# Main.net
KiCad netlist of a schematic drawn in Altium Designer
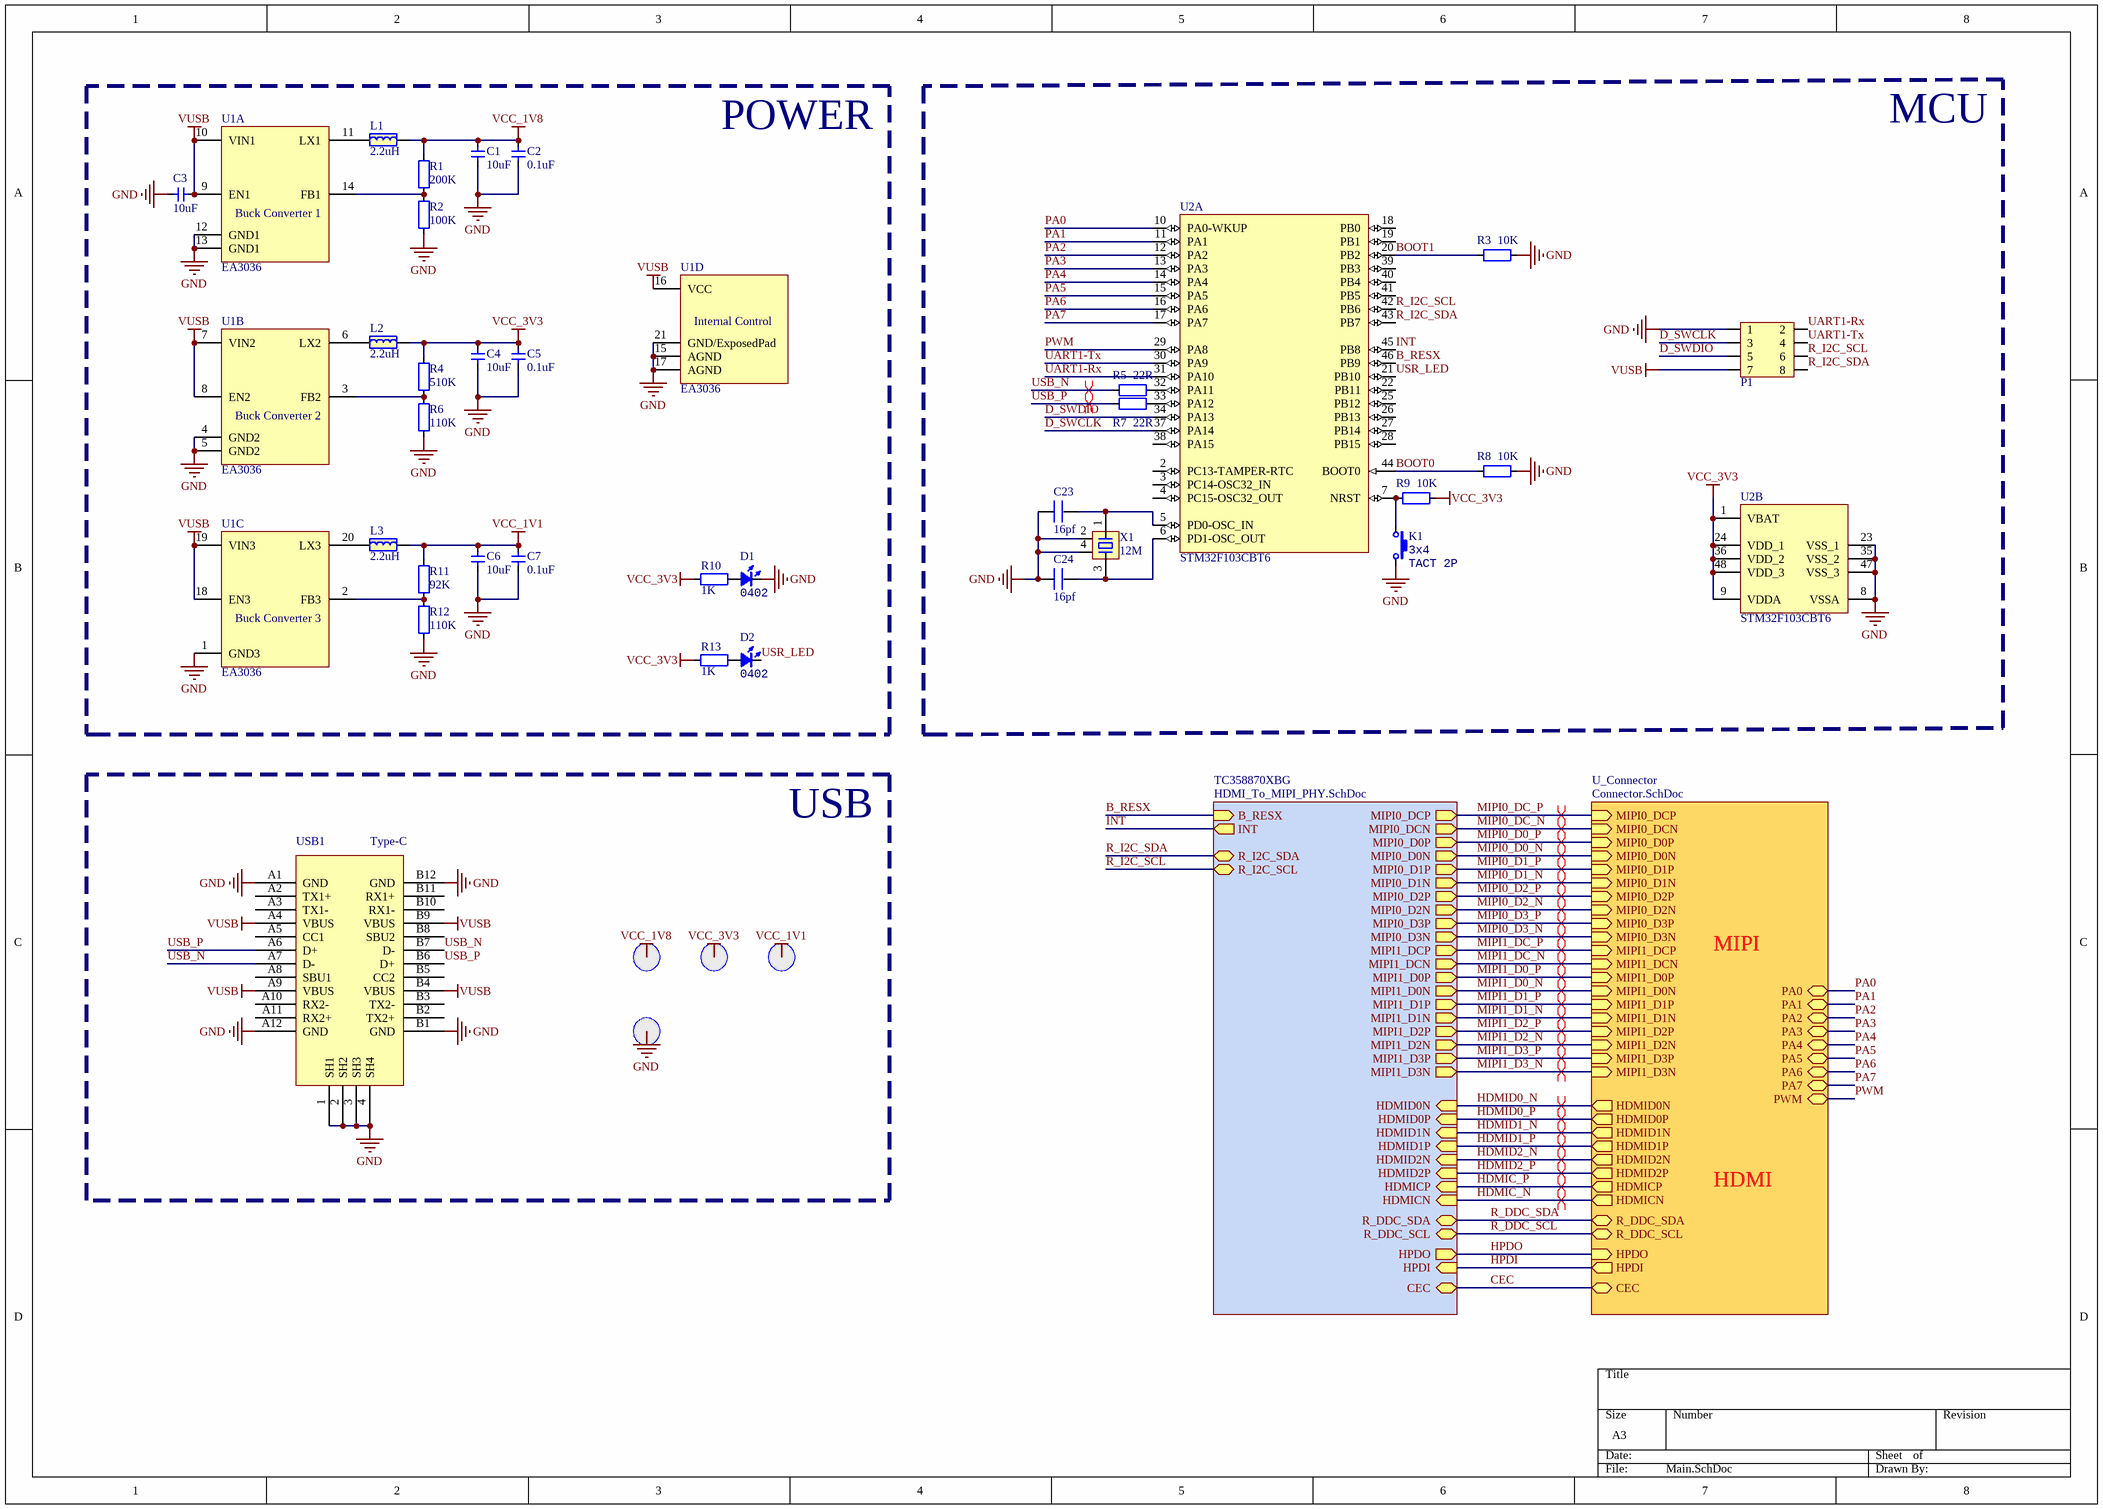
[diagram p0: Main.SchDoc]

(export (version "E")
  (design (tool "Eeschema 10.0.6"))
  (components
    (comp (ref "C1")
      (value "10uF")
      (footprint "CAP_0402")
      (description "Capacitor")
      (libsource (lib "MyPcbLib") (part "电容-0402"))
    )
    (comp (ref "C2")
      (value "0.1uF")
      (footprint "CAP_0402")
      (description "Capacitor")
      (libsource (lib "MyPcbLib") (part "电容-0402"))
    )
    (comp (ref "C3")
      (value "10uF")
      (footprint "CAP_0402")
      (description "Capacitor")
      (libsource (lib "MyPcbLib") (part "电容-0402"))
    )
    (comp (ref "C4")
      (value "10uF")
      (footprint "CAP_0402")
      (description "Capacitor")
      (libsource (lib "MyPcbLib") (part "电容-0402"))
    )
    (comp (ref "C5")
      (value "0.1uF")
      (footprint "CAP_0402")
      (description "Capacitor")
      (libsource (lib "MyPcbLib") (part "电容-0402"))
    )
    (comp (ref "C6")
      (value "10uF")
      (footprint "CAP_0402")
      (description "Capacitor")
      (libsource (lib "MyPcbLib") (part "电容-0402"))
    )
    (comp (ref "C7")
      (value "0.1uF")
      (footprint "CAP_0402")
      (description "Capacitor")
      (libsource (lib "MyPcbLib") (part "电容-0402"))
    )
    (comp (ref "C23") (value "16pf") (footprint "0603_CAP") (libsource (lib "STM32F429核心板封装库") (part "C")))
    (comp (ref "C24") (value "16pf") (footprint "0603_CAP") (libsource (lib "STM32F429核心板封装库") (part "C")))
    (comp (ref "D1")
      (value "color?")
      (footprint "SMDLED-0603")
      (description "LED")
      (fields (field (name "TYPE") "0402"))
      (libsource (lib "KitSprout") (part "LED_0402"))
    )
    (comp (ref "D2")
      (value "color?")
      (footprint "SMDLED-0603")
      (description "LED")
      (fields (field (name "TYPE") "0402"))
      (libsource (lib "KitSprout") (part "LED_0402"))
    )
    (comp (ref "K1")
      (value "3x4")
      (footprint "ButtonTACT_3x4x2_180H")
      (description "Button")
      (fields (field (name "TYPE") "TACT 2P") (field (name "Comment") "TACT 2P"))
      (libsource (lib "KitSprout") (part "ButtonTACT_3x4x2_180"))
    )
    (comp (ref "L1")
      (value "2.2uH")
      (footprint "2520-L")
      (description "磁珠")
      (libsource (lib "MyPcbLib") (part "电感-2520"))
    )
    (comp (ref "L2")
      (value "2.2uH")
      (footprint "2520-L")
      (description "磁珠")
      (libsource (lib "MyPcbLib") (part "电感-2520"))
    )
    (comp (ref "L3")
      (value "2.2uH")
      (footprint "2520-L")
      (description "磁珠")
      (libsource (lib "MyPcbLib") (part "电感-2520"))
    )
    (comp (ref "P1")
      (value "HDR2x4_2.54")
      (footprint "HDR2X4_2.54_180H")
      (description "Header")
      (libsource (lib "MyPcbLib") (part "HDR2x4_2.54"))
    )
    (comp (ref "R1")
      (value "200K")
      (footprint "RES_0402")
      (description "Resistor")
      (libsource (lib "MyPcbLib") (part "电阻-0402"))
    )
    (comp (ref "R2")
      (value "100K")
      (footprint "RES_0402")
      (description "Resistor")
      (libsource (lib "MyPcbLib") (part "电阻-0402"))
    )
    (comp (ref "R3")
      (value "10K")
      (footprint "RES_0402")
      (description "Resistor")
      (libsource (lib "") (part "电阻-0402_1"))
    )
    (comp (ref "R4")
      (value "510K")
      (footprint "RES_0402")
      (description "Resistor")
      (libsource (lib "MyPcbLib") (part "电阻-0402"))
    )
    (comp (ref "R5")
      (value "22R")
      (footprint "RES_0402")
      (description "Resistor")
      (libsource (lib "") (part "电阻-0402_1"))
    )
    (comp (ref "R6")
      (value "110K")
      (footprint "RES_0402")
      (description "Resistor")
      (libsource (lib "MyPcbLib") (part "电阻-0402"))
    )
    (comp (ref "R7")
      (value "22R")
      (footprint "RES_0402")
      (description "Resistor")
      (libsource (lib "") (part "电阻-0402_1"))
    )
    (comp (ref "R8")
      (value "10K")
      (footprint "RES_0402")
      (description "Resistor")
      (libsource (lib "") (part "电阻-0402_1"))
    )
    (comp (ref "R9")
      (value "10K")
      (footprint "RES_0402")
      (description "Resistor")
      (libsource (lib "") (part "电阻-0402_1"))
    )
    (comp (ref "R10")
      (value "1K")
      (footprint "RES_0402")
      (description "Resistor")
      (libsource (lib "") (part "电阻-0402_1"))
    )
    (comp (ref "R11")
      (value "92K")
      (footprint "RES_0402")
      (description "Resistor")
      (libsource (lib "MyPcbLib") (part "电阻-0402"))
    )
    (comp (ref "R12")
      (value "110K")
      (footprint "RES_0402")
      (description "Resistor")
      (libsource (lib "MyPcbLib") (part "电阻-0402"))
    )
    (comp (ref "R13")
      (value "1K")
      (footprint "RES_0402")
      (description "Resistor")
      (libsource (lib "") (part "电阻-0402_1"))
    )
    (comp (ref "T1") (value "测试点") (footprint "TEST_PT") (libsource (lib "MyPcbLib") (part "测试点")))
    (comp (ref "T2") (value "测试点") (footprint "TEST_PT") (libsource (lib "MyPcbLib") (part "测试点")))
    (comp (ref "T3") (value "测试点") (footprint "TEST_PT") (libsource (lib "MyPcbLib") (part "测试点")))
    (comp (ref "T4") (value "测试点") (footprint "TEST_PT") (libsource (lib "MyPcbLib") (part "测试点")))
    (comp (ref "U1") (value "EA3036") (footprint "QFN-20") (libsource (lib "mLib") (part "EA3036")))
    (comp (ref "U2")
      (value "STM32F103CBT6")
      (footprint "LQFP-48")
      (libsource (lib "STMicroelectronics STM32 F1") (part "STM32F103CBT6"))
    )
    (comp (ref "USB1")
      (value "Type-C")
      (footprint "Type-C-TOP")
      (libsource (lib "MyPcbLib") (part "USB-Type-C-TOP"))
    )
    (comp (ref "X1")
      (value "12M")
      (footprint "XTAL3225")
      (description "4脚无源晶振")
      (fields (field (name "版权归属") "源创客"))
      (libsource (lib "10.1 - 保险丝-晶振") (part "XTAL-4P"))
    )
  )
  (nets
    (net (code "1") (name "/BOOT0") (class "Default")
      (node (ref "R8") (pin "1") (pinfunction "1_1") (pintype "passive"))
      (node (ref "U2") (pin "44") (pinfunction "BOOT0_44") (pintype "input"))
    )
    (net (code "2") (name "/BOOT1") (class "Default")
      (node (ref "R3") (pin "1") (pinfunction "1_1") (pintype "passive"))
      (node (ref "U2") (pin "20") (pinfunction "PB2_20") (pintype "bidirectional"))
    )
    (net (code "3") (name "/B_RESX") (class "Default")
      (node (ref "U2") (pin "46") (pinfunction "PB9_46") (pintype "bidirectional"))
    )
    (net (code "5") (name "/D_SWCLK") (class "Default")
      (node (ref "P1") (pin "3") (pinfunction "3_3") (pintype "passive"))
      (node (ref "U2") (pin "37") (pinfunction "PA14_37") (pintype "bidirectional"))
    )
    (net (code "6") (name "/D_SWDIO") (class "Default")
      (node (ref "P1") (pin "5") (pinfunction "5_5") (pintype "passive"))
      (node (ref "U2") (pin "34") (pinfunction "PA13_34") (pintype "bidirectional"))
    )
    (net (code "17") (name "/INT") (class "Default")
      (node (ref "U2") (pin "45") (pinfunction "PB8_45") (pintype "bidirectional"))
    )
    (net (code "38") (name "/PA0") (class "Default")
      (node (ref "U2") (pin "10") (pinfunction "PA0-WKUP_10") (pintype "bidirectional"))
    )
    (net (code "39") (name "/PA1") (class "Default")
      (node (ref "U2") (pin "11") (pinfunction "PA1_11") (pintype "bidirectional"))
    )
    (net (code "40") (name "/PA2") (class "Default")
      (node (ref "U2") (pin "12") (pinfunction "PA2_12") (pintype "bidirectional"))
    )
    (net (code "41") (name "/PA3") (class "Default")
      (node (ref "U2") (pin "13") (pinfunction "PA3_13") (pintype "bidirectional"))
    )
    (net (code "42") (name "/PA4") (class "Default")
      (node (ref "U2") (pin "14") (pinfunction "PA4_14") (pintype "bidirectional"))
    )
    (net (code "43") (name "/PA5") (class "Default")
      (node (ref "U2") (pin "15") (pinfunction "PA5_15") (pintype "bidirectional"))
    )
    (net (code "44") (name "/PA6") (class "Default")
      (node (ref "U2") (pin "16") (pinfunction "PA6_16") (pintype "bidirectional"))
    )
    (net (code "45") (name "/PA7") (class "Default")
      (node (ref "U2") (pin "17") (pinfunction "PA7_17") (pintype "bidirectional"))
    )
    (net (code "46") (name "/PWM") (class "Default")
      (node (ref "U2") (pin "29") (pinfunction "PA8_29") (pintype "bidirectional"))
    )
    (net (code "49") (name "/R_I2C_SCL") (class "Default")
      (node (ref "P1") (pin "6") (pinfunction "6_6") (pintype "passive"))
      (node (ref "U2") (pin "42") (pinfunction "PB6_42") (pintype "bidirectional"))
    )
    (net (code "50") (name "/R_I2C_SDA") (class "Default")
      (node (ref "P1") (pin "8") (pinfunction "8_8") (pintype "passive"))
      (node (ref "U2") (pin "43") (pinfunction "PB7_43") (pintype "bidirectional"))
    )
    (net (code "51") (name "/UART1-Rx") (class "Default")
      (node (ref "P1") (pin "2") (pinfunction "2_2") (pintype "passive"))
      (node (ref "U2") (pin "31") (pinfunction "PA10_31") (pintype "bidirectional"))
    )
    (net (code "52") (name "/UART1-Tx") (class "Default")
      (node (ref "P1") (pin "4") (pinfunction "4_4") (pintype "passive"))
      (node (ref "U2") (pin "30") (pinfunction "PA9_30") (pintype "bidirectional"))
    )
    (net (code "53") (name "/USB_N") (class "Default")
      (node (ref "R5") (pin "1") (pinfunction "1_1") (pintype "passive"))
      (node (ref "USB1") (pin "A7") (pinfunction "D-_A7") (pintype "passive"))
      (node (ref "USB1") (pin "B7") (pinfunction "D-_B7") (pintype "passive"))
    )
    (net (code "54") (name "/USB_P") (class "Default")
      (node (ref "R7") (pin "1") (pinfunction "1_1") (pintype "passive"))
      (node (ref "USB1") (pin "A6") (pinfunction "D+_A6") (pintype "passive"))
      (node (ref "USB1") (pin "B6") (pinfunction "D+_B6") (pintype "passive"))
    )
    (net (code "55") (name "/USR_LED") (class "Default")
      (node (ref "D2") (pin "2") (pinfunction "K_2") (pintype "passive"))
      (node (ref "U2") (pin "21") (pinfunction "PB10_21") (pintype "bidirectional"))
    )
    (net (code "56") (name "GND") (class "Default")
      (node (ref "C1") (pin "1") (pinfunction "1_1") (pintype "passive"))
      (node (ref "C2") (pin "2") (pinfunction "2_2") (pintype "passive"))
      (node (ref "C23") (pin "2") (pintype "passive"))
      (node (ref "C24") (pin "2") (pintype "passive"))
      (node (ref "C3") (pin "1") (pinfunction "1_1") (pintype "passive"))
      (node (ref "C4") (pin "1") (pinfunction "1_1") (pintype "passive"))
      (node (ref "C5") (pin "2") (pinfunction "2_2") (pintype "passive"))
      (node (ref "C6") (pin "1") (pinfunction "1_1") (pintype "passive"))
      (node (ref "C7") (pin "2") (pinfunction "2_2") (pintype "passive"))
      (node (ref "D1") (pin "2") (pinfunction "K_2") (pintype "passive"))
      (node (ref "K1") (pin "2") (pinfunction "2_2") (pintype "passive"))
      (node (ref "P1") (pin "1") (pinfunction "1_1") (pintype "passive"))
      (node (ref "R12") (pin "1") (pinfunction "1_1") (pintype "passive"))
      (node (ref "R2") (pin "1") (pinfunction "1_1") (pintype "passive"))
      (node (ref "R3") (pin "2") (pinfunction "2_2") (pintype "passive"))
      (node (ref "R6") (pin "1") (pinfunction "1_1") (pintype "passive"))
      (node (ref "R8") (pin "2") (pinfunction "2_2") (pintype "passive"))
      (node (ref "T4") (pin "0") (pinfunction "0_0") (pintype "passive"))
      (node (ref "U1") (pin "1") (pinfunction "GND3_1") (pintype "power_in"))
      (node (ref "U1") (pin "12") (pinfunction "GND1_12") (pintype "power_in"))
      (node (ref "U1") (pin "13") (pinfunction "GND1_13") (pintype "power_in"))
      (node (ref "U1") (pin "15") (pinfunction "AGND_15") (pintype "power_in"))
      (node (ref "U1") (pin "17") (pinfunction "AGND_17") (pintype "power_in"))
      (node (ref "U1") (pin "21") (pinfunction "GND/ExposedPad_21") (pintype "power_in"))
      (node (ref "U1") (pin "4") (pinfunction "GND2_4") (pintype "power_in"))
      (node (ref "U1") (pin "5") (pinfunction "GND2_5") (pintype "power_in"))
      (node (ref "U2") (pin "23") (pinfunction "VSS_1_23") (pintype "power_in"))
      (node (ref "U2") (pin "35") (pinfunction "VSS_2_35") (pintype "power_in"))
      (node (ref "U2") (pin "47") (pinfunction "VSS_3_47") (pintype "power_in"))
      (node (ref "U2") (pin "8") (pinfunction "VSSA_8") (pintype "power_in"))
      (node (ref "USB1") (pin "1") (pinfunction "SH1_1") (pintype "passive"))
      (node (ref "USB1") (pin "2") (pinfunction "SH2_2") (pintype "passive"))
      (node (ref "USB1") (pin "3") (pinfunction "SH3_3") (pintype "passive"))
      (node (ref "USB1") (pin "4") (pinfunction "SH4_4") (pintype "passive"))
      (node (ref "USB1") (pin "A1") (pinfunction "GND_A1") (pintype "passive"))
      (node (ref "USB1") (pin "A12") (pinfunction "GND_A12") (pintype "passive"))
      (node (ref "USB1") (pin "B1") (pinfunction "GND_B1") (pintype "passive"))
      (node (ref "USB1") (pin "B12") (pinfunction "GND_B12") (pintype "passive"))
      (node (ref "X1") (pin "2") (pinfunction "2_2") (pintype "passive"))
      (node (ref "X1") (pin "4") (pinfunction "4_4") (pintype "passive"))
    )
    (net (code "57") (name "Net-(D1-A)") (class "Default")
      (node (ref "D1") (pin "1") (pinfunction "A_1") (pintype "passive"))
      (node (ref "R10") (pin "2") (pinfunction "2_2") (pintype "passive"))
    )
    (net (code "58") (name "Net-(D2-A)") (class "Default")
      (node (ref "D2") (pin "1") (pinfunction "A_1") (pintype "passive"))
      (node (ref "R13") (pin "2") (pinfunction "2_2") (pintype "passive"))
    )
    (net (code "59") (name "Net-(U1A-FB1)") (class "Default")
      (node (ref "R1") (pin "1") (pinfunction "1_1") (pintype "passive"))
      (node (ref "R2") (pin "2") (pinfunction "2_2") (pintype "passive"))
      (node (ref "U1") (pin "14") (pinfunction "FB1_14") (pintype "passive"))
    )
    (net (code "60") (name "Net-(U1A-LX1)") (class "Default")
      (node (ref "L1") (pin "1") (pintype "passive"))
      (node (ref "U1") (pin "11") (pinfunction "LX1_11") (pintype "passive"))
    )
    (net (code "61") (name "Net-(U1B-FB2)") (class "Default")
      (node (ref "R4") (pin "1") (pinfunction "1_1") (pintype "passive"))
      (node (ref "R6") (pin "2") (pinfunction "2_2") (pintype "passive"))
      (node (ref "U1") (pin "3") (pinfunction "FB2_3") (pintype "passive"))
    )
    (net (code "62") (name "Net-(U1B-LX2)") (class "Default")
      (node (ref "L2") (pin "1") (pintype "passive"))
      (node (ref "U1") (pin "6") (pinfunction "LX2_6") (pintype "passive"))
    )
    (net (code "63") (name "Net-(U1C-FB3)") (class "Default")
      (node (ref "R11") (pin "1") (pinfunction "1_1") (pintype "passive"))
      (node (ref "R12") (pin "2") (pinfunction "2_2") (pintype "passive"))
      (node (ref "U1") (pin "2") (pinfunction "FB3_2") (pintype "passive"))
    )
    (net (code "64") (name "Net-(U1C-LX3)") (class "Default")
      (node (ref "L3") (pin "1") (pintype "passive"))
      (node (ref "U1") (pin "20") (pinfunction "LX3_20") (pintype "passive"))
    )
    (net (code "65") (name "Net-(U2A-NRST)") (class "Default")
      (node (ref "K1") (pin "1") (pinfunction "1_1") (pintype "passive"))
      (node (ref "R9") (pin "1") (pinfunction "1_1") (pintype "passive"))
      (node (ref "U2") (pin "7") (pinfunction "NRST_7") (pintype "bidirectional"))
    )
    (net (code "66") (name "Net-(U2A-PA11)") (class "Default")
      (node (ref "R5") (pin "2") (pinfunction "2_2") (pintype "passive"))
      (node (ref "U2") (pin "32") (pinfunction "PA11_32") (pintype "bidirectional"))
    )
    (net (code "67") (name "Net-(U2A-PA12)") (class "Default")
      (node (ref "R7") (pin "2") (pinfunction "2_2") (pintype "passive"))
      (node (ref "U2") (pin "33") (pinfunction "PA12_33") (pintype "bidirectional"))
    )
    (net (code "68") (name "Net-(U2A-PD0-OSC_IN)") (class "Default")
      (node (ref "C23") (pin "1") (pintype "passive"))
      (node (ref "U2") (pin "5") (pinfunction "PD0-OSC_IN_5") (pintype "bidirectional"))
      (node (ref "X1") (pin "1") (pinfunction "1_1") (pintype "passive"))
    )
    (net (code "69") (name "Net-(U2A-PD1-OSC_OUT)") (class "Default")
      (node (ref "C24") (pin "1") (pintype "passive"))
      (node (ref "U2") (pin "6") (pinfunction "PD1-OSC_OUT_6") (pintype "bidirectional"))
      (node (ref "X1") (pin "3") (pinfunction "3_3") (pintype "passive"))
    )
    (net (code "70") (name "VCC_1V1") (class "Default")
      (node (ref "C6") (pin "2") (pinfunction "2_2") (pintype "passive"))
      (node (ref "C7") (pin "1") (pinfunction "1_1") (pintype "passive"))
      (node (ref "L3") (pin "2") (pinfunction "2_2") (pintype "passive"))
      (node (ref "R11") (pin "2") (pinfunction "2_2") (pintype "passive"))
      (node (ref "T3") (pin "0") (pinfunction "0_0") (pintype "passive"))
    )
    (net (code "71") (name "VCC_1V8") (class "Default")
      (node (ref "C1") (pin "2") (pinfunction "2_2") (pintype "passive"))
      (node (ref "C2") (pin "1") (pinfunction "1_1") (pintype "passive"))
      (node (ref "L1") (pin "2") (pinfunction "2_2") (pintype "passive"))
      (node (ref "R1") (pin "2") (pinfunction "2_2") (pintype "passive"))
      (node (ref "T1") (pin "0") (pinfunction "0_0") (pintype "passive"))
    )
    (net (code "72") (name "VCC_3V3") (class "Default")
      (node (ref "C4") (pin "2") (pinfunction "2_2") (pintype "passive"))
      (node (ref "C5") (pin "1") (pinfunction "1_1") (pintype "passive"))
      (node (ref "L2") (pin "2") (pinfunction "2_2") (pintype "passive"))
      (node (ref "R10") (pin "1") (pinfunction "1_1") (pintype "passive"))
      (node (ref "R13") (pin "1") (pinfunction "1_1") (pintype "passive"))
      (node (ref "R4") (pin "2") (pinfunction "2_2") (pintype "passive"))
      (node (ref "R9") (pin "2") (pinfunction "2_2") (pintype "passive"))
      (node (ref "T2") (pin "0") (pinfunction "0_0") (pintype "passive"))
      (node (ref "U2") (pin "1") (pinfunction "VBAT_1") (pintype "power_in"))
      (node (ref "U2") (pin "24") (pinfunction "VDD_1_24") (pintype "power_in"))
      (node (ref "U2") (pin "36") (pinfunction "VDD_2_36") (pintype "power_in"))
      (node (ref "U2") (pin "48") (pinfunction "VDD_3_48") (pintype "power_in"))
      (node (ref "U2") (pin "9") (pinfunction "VDDA_9") (pintype "power_in"))
    )
    (net (code "73") (name "VUSB") (class "Default")
      (node (ref "C3") (pin "2") (pinfunction "2_2") (pintype "passive"))
      (node (ref "P1") (pin "7") (pinfunction "7_7") (pintype "passive"))
      (node (ref "U1") (pin "10") (pinfunction "VIN1_10") (pintype "power_in"))
      (node (ref "U1") (pin "16") (pinfunction "VCC_16") (pintype "power_in"))
      (node (ref "U1") (pin "18") (pinfunction "EN3_18") (pintype "passive"))
      (node (ref "U1") (pin "19") (pinfunction "VIN3_19") (pintype "power_in"))
      (node (ref "U1") (pin "7") (pinfunction "VIN2_7") (pintype "power_in"))
      (node (ref "U1") (pin "8") (pinfunction "EN2_8") (pintype "passive"))
      (node (ref "U1") (pin "9") (pinfunction "EN1_9") (pintype "passive"))
      (node (ref "USB1") (pin "A4") (pinfunction "VBUS_A4") (pintype "passive"))
      (node (ref "USB1") (pin "A9") (pinfunction "VBUS_A9") (pintype "passive"))
      (node (ref "USB1") (pin "B4") (pinfunction "VBUS_B4") (pintype "passive"))
      (node (ref "USB1") (pin "B9") (pinfunction "VBUS_B9") (pintype "passive"))
    )
    (net (code "74") (name "unconnected-(U2A-PA15-Pad38)") (class "Default")
      (node (ref "U2") (pin "38") (pinfunction "PA15_38") (pintype "bidirectional"))
    )
    (net (code "75") (name "unconnected-(U2A-PB0-Pad18)") (class "Default")
      (node (ref "U2") (pin "18") (pinfunction "PB0_18") (pintype "bidirectional"))
    )
    (net (code "76") (name "unconnected-(U2A-PB1-Pad19)") (class "Default")
      (node (ref "U2") (pin "19") (pinfunction "PB1_19") (pintype "bidirectional"))
    )
    (net (code "77") (name "unconnected-(U2A-PB3-Pad39)") (class "Default")
      (node (ref "U2") (pin "39") (pinfunction "PB3_39") (pintype "bidirectional"))
    )
    (net (code "78") (name "unconnected-(U2A-PB4-Pad40)") (class "Default")
      (node (ref "U2") (pin "40") (pinfunction "PB4_40") (pintype "bidirectional"))
    )
    (net (code "79") (name "unconnected-(U2A-PB5-Pad41)") (class "Default")
      (node (ref "U2") (pin "41") (pinfunction "PB5_41") (pintype "bidirectional"))
    )
    (net (code "80") (name "unconnected-(U2A-PB11-Pad22)") (class "Default")
      (node (ref "U2") (pin "22") (pinfunction "PB11_22") (pintype "bidirectional"))
    )
    (net (code "81") (name "unconnected-(U2A-PB12-Pad25)") (class "Default")
      (node (ref "U2") (pin "25") (pinfunction "PB12_25") (pintype "bidirectional"))
    )
    (net (code "82") (name "unconnected-(U2A-PB13-Pad26)") (class "Default")
      (node (ref "U2") (pin "26") (pinfunction "PB13_26") (pintype "bidirectional"))
    )
    (net (code "83") (name "unconnected-(U2A-PB14-Pad27)") (class "Default")
      (node (ref "U2") (pin "27") (pinfunction "PB14_27") (pintype "bidirectional"))
    )
    (net (code "84") (name "unconnected-(U2A-PB15-Pad28)") (class "Default")
      (node (ref "U2") (pin "28") (pinfunction "PB15_28") (pintype "bidirectional"))
    )
    (net (code "85") (name "unconnected-(U2A-PC13-TAMPER-RTC-Pad2)") (class "Default")
      (node (ref "U2") (pin "2") (pinfunction "PC13-TAMPER-RTC_2") (pintype "bidirectional"))
    )
    (net (code "86") (name "unconnected-(U2A-PC14-OSC32_IN-Pad3)") (class "Default")
      (node (ref "U2") (pin "3") (pinfunction "PC14-OSC32_IN_3") (pintype "bidirectional"))
    )
    (net (code "87") (name "unconnected-(U2A-PC15-OSC32_OUT-Pad4)") (class "Default")
      (node (ref "U2") (pin "4") (pinfunction "PC15-OSC32_OUT_4") (pintype "bidirectional"))
    )
    (net (code "88") (name "unconnected-(USB1-CC1-PadA5)") (class "Default")
      (node (ref "USB1") (pin "A5") (pinfunction "CC1_A5") (pintype "passive"))
    )
    (net (code "89") (name "unconnected-(USB1-CC2-PadB5)") (class "Default")
      (node (ref "USB1") (pin "B5") (pinfunction "CC2_B5") (pintype "passive"))
    )
    (net (code "90") (name "unconnected-(USB1-RX1+-PadB11)") (class "Default")
      (node (ref "USB1") (pin "B11") (pinfunction "RX1+_B11") (pintype "passive"))
    )
    (net (code "91") (name "unconnected-(USB1-RX1--PadB10)") (class "Default")
      (node (ref "USB1") (pin "B10") (pinfunction "RX1-_B10") (pintype "passive"))
    )
    (net (code "92") (name "unconnected-(USB1-RX2+-PadA11)") (class "Default")
      (node (ref "USB1") (pin "A11") (pinfunction "RX2+_A11") (pintype "passive"))
    )
    (net (code "93") (name "unconnected-(USB1-RX2--PadA10)") (class "Default")
      (node (ref "USB1") (pin "A10") (pinfunction "RX2-_A10") (pintype "passive"))
    )
    (net (code "94") (name "unconnected-(USB1-SBU1-PadA8)") (class "Default")
      (node (ref "USB1") (pin "A8") (pinfunction "SBU1_A8") (pintype "passive"))
    )
    (net (code "95") (name "unconnected-(USB1-SBU2-PadB8)") (class "Default")
      (node (ref "USB1") (pin "B8") (pinfunction "SBU2_B8") (pintype "passive"))
    )
    (net (code "96") (name "unconnected-(USB1-TX1+-PadA2)") (class "Default")
      (node (ref "USB1") (pin "A2") (pinfunction "TX1+_A2") (pintype "passive"))
    )
    (net (code "97") (name "unconnected-(USB1-TX1--PadA3)") (class "Default")
      (node (ref "USB1") (pin "A3") (pinfunction "TX1-_A3") (pintype "passive"))
    )
    (net (code "98") (name "unconnected-(USB1-TX2+-PadB2)") (class "Default")
      (node (ref "USB1") (pin "B2") (pinfunction "TX2+_B2") (pintype "passive"))
    )
    (net (code "99") (name "unconnected-(USB1-TX2--PadB3)") (class "Default")
      (node (ref "USB1") (pin "B3") (pinfunction "TX2-_B3") (pintype "passive"))
    )
  )
)
